# 1uprava2.net
KiCad netlist of a schematic drawn in EAGLE
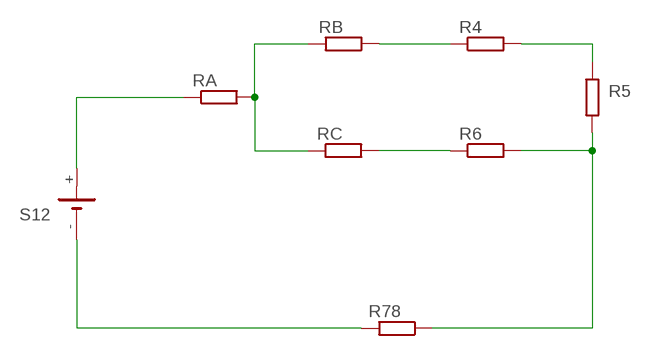
[diagram p0: schematic, sheet 1]

(export (version "E")
  (design (tool "Eeschema 10.0.6"))
  (components
    (comp (ref "R4")
      (value "310R")
      (footprint "eagle-import:0204_7")
      (libsource (lib "eagle-import") (part "R-EU_0204/7"))
    )
    (comp (ref "R5")
      (value "575R")
      (footprint "eagle-import:0204_7")
      (libsource (lib "eagle-import") (part "R-EU_0204/7"))
    )
    (comp (ref "R6")
      (value "870R")
      (footprint "eagle-import:0204_7")
      (libsource (lib "eagle-import") (part "R-EU_0204/7"))
    )
    (comp (ref "R78")
      (value "355R")
      (footprint "eagle-import:0204_7")
      (libsource (lib "eagle-import") (part "R-EU_0204/7"))
    )
    (comp (ref "RA")
      (value "680R")
      (footprint "eagle-import:0204_7")
      (libsource (lib "eagle-import") (part "R-EU_0204/7"))
    )
    (comp (ref "RB")
      (value "260R")
      (footprint "eagle-import:0204_7")
      (libsource (lib "eagle-import") (part "R-EU_0204/7"))
    )
    (comp (ref "RC")
      (value "600R")
      (footprint "eagle-import:0204_7")
      (libsource (lib "eagle-import") (part "R-EU_0204/7"))
    )
    (comp (ref "S12")
      (value "135V")
      (footprint "eagle-import:CH291-1220LF")
      (libsource (lib "eagle-import") (part "CH291-1220LF"))
    )
  )
  (nets
    (net (code "1") (name "Net-(R4-Pad1)") (class "Default")
      (node (ref "R4") (pin "1") (pinfunction "1_1") (pintype "passive"))
      (node (ref "RB") (pin "1") (pinfunction "1_1") (pintype "passive"))
    )
    (net (code "2") (name "Net-(R4-Pad2)") (class "Default")
      (node (ref "R4") (pin "2") (pinfunction "2_2") (pintype "passive"))
      (node (ref "R5") (pin "1") (pinfunction "1_1") (pintype "passive"))
    )
    (net (code "3") (name "Net-(R5-Pad2)") (class "Default")
      (node (ref "R5") (pin "2") (pinfunction "2_2") (pintype "passive"))
      (node (ref "R6") (pin "2") (pinfunction "2_2") (pintype "passive"))
      (node (ref "R78") (pin "1") (pinfunction "1_1") (pintype "passive"))
    )
    (net (code "4") (name "Net-(R6-Pad1)") (class "Default")
      (node (ref "R6") (pin "1") (pinfunction "1_1") (pintype "passive"))
      (node (ref "RC") (pin "2") (pinfunction "2_2") (pintype "passive"))
    )
    (net (code "5") (name "Net-(R78-Pad2)") (class "Default")
      (node (ref "R78") (pin "2") (pinfunction "2_2") (pintype "passive"))
      (node (ref "S12") (pin "-") (pinfunction "-_-") (pintype "passive"))
    )
    (net (code "6") (name "Net-(RA-Pad1)") (class "Default")
      (node (ref "RA") (pin "1") (pinfunction "1_1") (pintype "passive"))
      (node (ref "S12") (pin "+") (pinfunction "+_+") (pintype "passive"))
    )
    (net (code "7") (name "Net-(RA-Pad2)") (class "Default")
      (node (ref "RA") (pin "2") (pinfunction "2_2") (pintype "passive"))
      (node (ref "RB") (pin "2") (pinfunction "2_2") (pintype "passive"))
      (node (ref "RC") (pin "1") (pinfunction "1_1") (pintype "passive"))
    )
  )
)
